# BigBus_XXL_Breed_Error.net
KiCad netlist of a schematic drawn in EAGLE
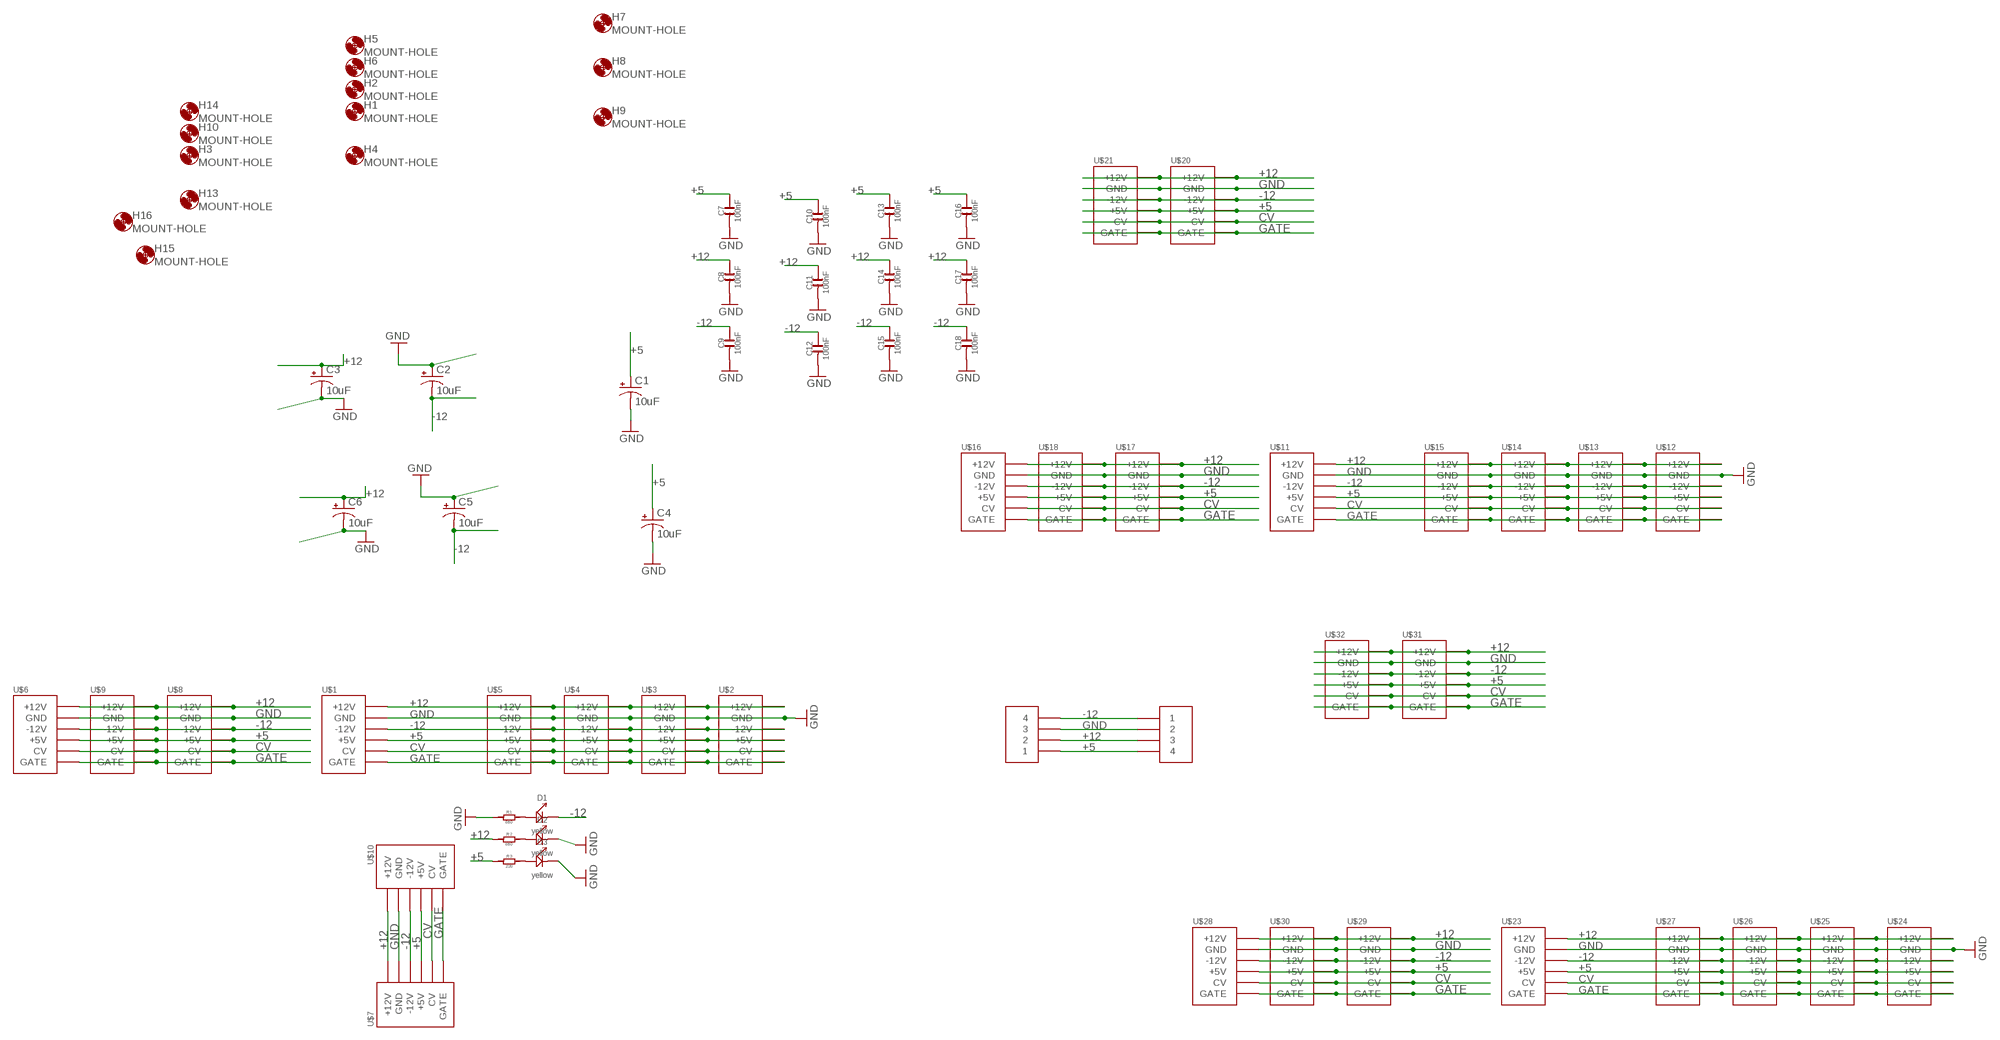
[diagram p0: schematic, sheet 1]

(export (version "E")
  (design (tool "Eeschema 10.0.6"))
  (components
    (comp (ref "C1")
      (value "10uF")
      (footprint "eagle-import:PANASONIC_D")
      (libsource (lib "eagle-import") (part "CAP_POLD"))
    )
    (comp (ref "C2")
      (value "10uF")
      (footprint "eagle-import:PANASONIC_D")
      (libsource (lib "eagle-import") (part "CAP_POLD"))
    )
    (comp (ref "C3")
      (value "10uF")
      (footprint "eagle-import:PANASONIC_D")
      (libsource (lib "eagle-import") (part "CAP_POLD"))
    )
    (comp (ref "C4")
      (value "10uF")
      (footprint "eagle-import:PANASONIC_D")
      (libsource (lib "eagle-import") (part "CAP_POLD"))
    )
    (comp (ref "C5")
      (value "10uF")
      (footprint "eagle-import:PANASONIC_D")
      (libsource (lib "eagle-import") (part "CAP_POLD"))
    )
    (comp (ref "C6")
      (value "10uF")
      (footprint "eagle-import:PANASONIC_D")
      (libsource (lib "eagle-import") (part "CAP_POLD"))
    )
    (comp (ref "C7")
      (value "100nF")
      (footprint "eagle-import:C0603")
      (libsource (lib "eagle-import") (part "C-0603"))
    )
    (comp (ref "C8")
      (value "100nF")
      (footprint "eagle-import:C0603")
      (libsource (lib "eagle-import") (part "C-0603"))
    )
    (comp (ref "C9")
      (value "100nF")
      (footprint "eagle-import:C0603")
      (libsource (lib "eagle-import") (part "C-0603"))
    )
    (comp (ref "C10")
      (value "100nF")
      (footprint "eagle-import:C0603")
      (libsource (lib "eagle-import") (part "C-0603"))
    )
    (comp (ref "C11")
      (value "100nF")
      (footprint "eagle-import:C0603")
      (libsource (lib "eagle-import") (part "C-0603"))
    )
    (comp (ref "C12")
      (value "100nF")
      (footprint "eagle-import:C0603")
      (libsource (lib "eagle-import") (part "C-0603"))
    )
    (comp (ref "C13")
      (value "100nF")
      (footprint "eagle-import:C0603")
      (libsource (lib "eagle-import") (part "C-0603"))
    )
    (comp (ref "C14")
      (value "100nF")
      (footprint "eagle-import:C0603")
      (libsource (lib "eagle-import") (part "C-0603"))
    )
    (comp (ref "C15")
      (value "100nF")
      (footprint "eagle-import:C0603")
      (libsource (lib "eagle-import") (part "C-0603"))
    )
    (comp (ref "C16")
      (value "100nF")
      (footprint "eagle-import:C0603")
      (libsource (lib "eagle-import") (part "C-0603"))
    )
    (comp (ref "C17")
      (value "100nF")
      (footprint "eagle-import:C0603")
      (libsource (lib "eagle-import") (part "C-0603"))
    )
    (comp (ref "C18")
      (value "100nF")
      (footprint "eagle-import:C0603")
      (libsource (lib "eagle-import") (part "C-0603"))
    )
    (comp (ref "D1")
      (value "yellow")
      (footprint "eagle-import:LED0603")
      (libsource (lib "eagle-import") (part "LED"))
    )
    (comp (ref "D2")
      (value "yellow")
      (footprint "eagle-import:LED0603")
      (libsource (lib "eagle-import") (part "LED"))
    )
    (comp (ref "D3")
      (value "yellow")
      (footprint "eagle-import:LED0603")
      (libsource (lib "eagle-import") (part "LED"))
    )
    (comp (ref "H1")
      (value "MOUNT-HOLE")
      (footprint "eagle-import:3.2-NOMARKINGS-SMALLSAFEZONE")
      (libsource (lib "eagle-import") (part "MOUNT-HOLE"))
    )
    (comp (ref "H2")
      (value "MOUNT-HOLE")
      (footprint "eagle-import:3.2-NOMARKINGS-SMALLSAFEZONE")
      (libsource (lib "eagle-import") (part "MOUNT-HOLE"))
    )
    (comp (ref "H3")
      (value "MOUNT-HOLE")
      (footprint "eagle-import:3.2-NOMARKINGS-SMALLSAFEZONE")
      (libsource (lib "eagle-import") (part "MOUNT-HOLE"))
    )
    (comp (ref "H4")
      (value "MOUNT-HOLE")
      (footprint "eagle-import:3.2-NOMARKINGS-SMALLSAFEZONE")
      (libsource (lib "eagle-import") (part "MOUNT-HOLE"))
    )
    (comp (ref "H5")
      (value "MOUNT-HOLE")
      (footprint "eagle-import:3.2-NOMARKINGS-SMALLSAFEZONE")
      (libsource (lib "eagle-import") (part "MOUNT-HOLE"))
    )
    (comp (ref "H6")
      (value "MOUNT-HOLE")
      (footprint "eagle-import:3.2-NOMARKINGS-SMALLSAFEZONE")
      (libsource (lib "eagle-import") (part "MOUNT-HOLE"))
    )
    (comp (ref "H7")
      (value "MOUNT-HOLE")
      (footprint "eagle-import:3.2-NOMARKINGS-SMALLSAFEZONE")
      (libsource (lib "eagle-import") (part "MOUNT-HOLE"))
    )
    (comp (ref "H8")
      (value "MOUNT-HOLE")
      (footprint "eagle-import:3.2-NOMARKINGS-SMALLSAFEZONE")
      (libsource (lib "eagle-import") (part "MOUNT-HOLE"))
    )
    (comp (ref "H9")
      (value "MOUNT-HOLE")
      (footprint "eagle-import:3.2-NOMARKINGS-SMALLSAFEZONE")
      (libsource (lib "eagle-import") (part "MOUNT-HOLE"))
    )
    (comp (ref "H10")
      (value "MOUNT-HOLE")
      (footprint "eagle-import:3.2-NOMARKINGS-SMALLSAFEZONE")
      (libsource (lib "eagle-import") (part "MOUNT-HOLE"))
    )
    (comp (ref "H13")
      (value "MOUNT-HOLE")
      (footprint "eagle-import:3.2-NOMARKINGS-SMALLSAFEZONE")
      (libsource (lib "eagle-import") (part "MOUNT-HOLE"))
    )
    (comp (ref "H14")
      (value "MOUNT-HOLE")
      (footprint "eagle-import:3.2-NOMARKINGS-SMALLSAFEZONE")
      (libsource (lib "eagle-import") (part "MOUNT-HOLE"))
    )
    (comp (ref "H15")
      (value "MOUNT-HOLE")
      (footprint "eagle-import:3.2-NOMARKINGS-SMALLSAFEZONE")
      (libsource (lib "eagle-import") (part "MOUNT-HOLE"))
    )
    (comp (ref "H16")
      (value "MOUNT-HOLE")
      (footprint "eagle-import:3.2-NOMARKINGS-SMALLSAFEZONE")
      (libsource (lib "eagle-import") (part "MOUNT-HOLE"))
    )
    (comp (ref "R1")
      (value "680")
      (footprint "eagle-import:R0603")
      (libsource (lib "eagle-import") (part "R-0603"))
    )
    (comp (ref "R2")
      (value "680")
      (footprint "eagle-import:R0603")
      (libsource (lib "eagle-import") (part "R-0603"))
    )
    (comp (ref "R3")
      (value "220")
      (footprint "eagle-import:R0603")
      (libsource (lib "eagle-import") (part "R-0603"))
    )
    (comp (ref "U$1")
      (value "POWER_SHROUDED_NOTEXT")
      (footprint "eagle-import:POWER_16_SHROUDED_NOTEXT")
      (libsource (lib "eagle-import") (part "POWER_SHROUDED_NOTEXT"))
    )
    (comp (ref "U$2")
      (value "POWER_SHROUDED_NOTEXT")
      (footprint "eagle-import:POWER_16_SHROUDED_NOTEXT")
      (libsource (lib "eagle-import") (part "POWER_SHROUDED_NOTEXT"))
    )
    (comp (ref "U$3")
      (value "POWER_SHROUDED_NOTEXT")
      (footprint "eagle-import:POWER_16_SHROUDED_NOTEXT")
      (libsource (lib "eagle-import") (part "POWER_SHROUDED_NOTEXT"))
    )
    (comp (ref "U$4")
      (value "POWER_SHROUDED_NOTEXT")
      (footprint "eagle-import:POWER_16_SHROUDED_NOTEXT")
      (libsource (lib "eagle-import") (part "POWER_SHROUDED_NOTEXT"))
    )
    (comp (ref "U$5")
      (value "POWER_SHROUDED_NOTEXT")
      (footprint "eagle-import:POWER_16_SHROUDED_NOTEXT")
      (libsource (lib "eagle-import") (part "POWER_SHROUDED_NOTEXT"))
    )
    (comp (ref "U$6")
      (value "POWER_SHROUDED_NOTEXT")
      (footprint "eagle-import:POWER_16_SHROUDED_NOTEXT")
      (libsource (lib "eagle-import") (part "POWER_SHROUDED_NOTEXT"))
    )
    (comp (ref "U$7")
      (value "POWER_SHROUDED_NOTEXT")
      (footprint "eagle-import:POWER_16_SHROUDED_NOTEXT")
      (libsource (lib "eagle-import") (part "POWER_SHROUDED_NOTEXT"))
    )
    (comp (ref "U$8")
      (value "POWER_SHROUDED_NOTEXT")
      (footprint "eagle-import:POWER_16_SHROUDED_NOTEXT")
      (libsource (lib "eagle-import") (part "POWER_SHROUDED_NOTEXT"))
    )
    (comp (ref "U$9")
      (value "POWER_SHROUDED_NOTEXT")
      (footprint "eagle-import:POWER_16_SHROUDED_NOTEXT")
      (libsource (lib "eagle-import") (part "POWER_SHROUDED_NOTEXT"))
    )
    (comp (ref "U$10")
      (value "POWER_SHROUDED_NOTEXT")
      (footprint "eagle-import:POWER_16_SHROUDED_NOTEXT")
      (libsource (lib "eagle-import") (part "POWER_SHROUDED_NOTEXT"))
    )
    (comp (ref "U$11")
      (value "POWER_SHROUDED_NOTEXT")
      (footprint "eagle-import:POWER_16_SHROUDED_NOTEXT")
      (libsource (lib "eagle-import") (part "POWER_SHROUDED_NOTEXT"))
    )
    (comp (ref "U$12")
      (value "POWER_SHROUDED_NOTEXT")
      (footprint "eagle-import:POWER_16_SHROUDED_NOTEXT")
      (libsource (lib "eagle-import") (part "POWER_SHROUDED_NOTEXT"))
    )
    (comp (ref "U$13")
      (value "POWER_SHROUDED_NOTEXT")
      (footprint "eagle-import:POWER_16_SHROUDED_NOTEXT")
      (libsource (lib "eagle-import") (part "POWER_SHROUDED_NOTEXT"))
    )
    (comp (ref "U$14")
      (value "POWER_SHROUDED_NOTEXT")
      (footprint "eagle-import:POWER_16_SHROUDED_NOTEXT")
      (libsource (lib "eagle-import") (part "POWER_SHROUDED_NOTEXT"))
    )
    (comp (ref "U$15")
      (value "POWER_SHROUDED_NOTEXT")
      (footprint "eagle-import:POWER_16_SHROUDED_NOTEXT")
      (libsource (lib "eagle-import") (part "POWER_SHROUDED_NOTEXT"))
    )
    (comp (ref "U$16")
      (value "POWER_SHROUDED_NOTEXT")
      (footprint "eagle-import:POWER_16_SHROUDED_NOTEXT")
      (libsource (lib "eagle-import") (part "POWER_SHROUDED_NOTEXT"))
    )
    (comp (ref "U$17")
      (value "POWER_SHROUDED_NOTEXT")
      (footprint "eagle-import:POWER_16_SHROUDED_NOTEXT")
      (libsource (lib "eagle-import") (part "POWER_SHROUDED_NOTEXT"))
    )
    (comp (ref "U$18")
      (value "POWER_SHROUDED_NOTEXT")
      (footprint "eagle-import:POWER_16_SHROUDED_NOTEXT")
      (libsource (lib "eagle-import") (part "POWER_SHROUDED_NOTEXT"))
    )
    (comp (ref "U$19")
      (value "4PIN5MM")
      (footprint "eagle-import:4PIN5MM")
      (libsource (lib "eagle-import") (part "4PIN5MM"))
    )
    (comp (ref "U$20")
      (value "POWER_SHROUDED_NOTEXT")
      (footprint "eagle-import:POWER_16_SHROUDED_NOTEXT")
      (libsource (lib "eagle-import") (part "POWER_SHROUDED_NOTEXT"))
    )
    (comp (ref "U$21")
      (value "POWER_SHROUDED_NOTEXT")
      (footprint "eagle-import:POWER_16_SHROUDED_NOTEXT")
      (libsource (lib "eagle-import") (part "POWER_SHROUDED_NOTEXT"))
    )
    (comp (ref "U$22")
      (value "4PIN5MM")
      (footprint "eagle-import:4PIN5MM")
      (libsource (lib "eagle-import") (part "4PIN5MM"))
    )
    (comp (ref "U$23")
      (value "POWER_SHROUDED_NOTEXT")
      (footprint "eagle-import:POWER_16_SHROUDED_NOTEXT")
      (libsource (lib "eagle-import") (part "POWER_SHROUDED_NOTEXT"))
    )
    (comp (ref "U$24")
      (value "POWER_SHROUDED_NOTEXT")
      (footprint "eagle-import:POWER_16_SHROUDED_NOTEXT")
      (libsource (lib "eagle-import") (part "POWER_SHROUDED_NOTEXT"))
    )
    (comp (ref "U$25")
      (value "POWER_SHROUDED_NOTEXT")
      (footprint "eagle-import:POWER_16_SHROUDED_NOTEXT")
      (libsource (lib "eagle-import") (part "POWER_SHROUDED_NOTEXT"))
    )
    (comp (ref "U$26")
      (value "POWER_SHROUDED_NOTEXT")
      (footprint "eagle-import:POWER_16_SHROUDED_NOTEXT")
      (libsource (lib "eagle-import") (part "POWER_SHROUDED_NOTEXT"))
    )
    (comp (ref "U$27")
      (value "POWER_SHROUDED_NOTEXT")
      (footprint "eagle-import:POWER_16_SHROUDED_NOTEXT")
      (libsource (lib "eagle-import") (part "POWER_SHROUDED_NOTEXT"))
    )
    (comp (ref "U$28")
      (value "POWER_SHROUDED_NOTEXT")
      (footprint "eagle-import:POWER_16_SHROUDED_NOTEXT")
      (libsource (lib "eagle-import") (part "POWER_SHROUDED_NOTEXT"))
    )
    (comp (ref "U$29")
      (value "POWER_SHROUDED_NOTEXT")
      (footprint "eagle-import:POWER_16_SHROUDED_NOTEXT")
      (libsource (lib "eagle-import") (part "POWER_SHROUDED_NOTEXT"))
    )
    (comp (ref "U$30")
      (value "POWER_SHROUDED_NOTEXT")
      (footprint "eagle-import:POWER_16_SHROUDED_NOTEXT")
      (libsource (lib "eagle-import") (part "POWER_SHROUDED_NOTEXT"))
    )
    (comp (ref "U$31")
      (value "POWER_SHROUDED_NOTEXT")
      (footprint "eagle-import:POWER_16_SHROUDED_NOTEXT")
      (libsource (lib "eagle-import") (part "POWER_SHROUDED_NOTEXT"))
    )
    (comp (ref "U$32")
      (value "POWER_SHROUDED_NOTEXT")
      (footprint "eagle-import:POWER_16_SHROUDED_NOTEXT")
      (libsource (lib "eagle-import") (part "POWER_SHROUDED_NOTEXT"))
    )
  )
  (nets
    (net (code "1") (name "/+5") (class "Default")
      (node (ref "C1") (pin "+") (pinfunction "+_+") (pintype "passive"))
      (node (ref "C10") (pin "2") (pinfunction "2_2") (pintype "bidirectional"))
      (node (ref "C13") (pin "2") (pinfunction "2_2") (pintype "bidirectional"))
      (node (ref "C16") (pin "2") (pinfunction "2_2") (pintype "bidirectional"))
      (node (ref "C4") (pin "+") (pinfunction "+_+") (pintype "passive"))
      (node (ref "C7") (pin "2") (pinfunction "2_2") (pintype "bidirectional"))
      (node (ref "R3") (pin "1") (pinfunction "1_1") (pintype "bidirectional"))
      (node (ref "U$1") (pin "11") (pinfunction "+5V_11") (pintype "bidirectional"))
      (node (ref "U$1") (pin "12") (pinfunction "+5V_12") (pintype "bidirectional"))
      (node (ref "U$10") (pin "11") (pinfunction "+5V_11") (pintype "bidirectional"))
      (node (ref "U$10") (pin "12") (pinfunction "+5V_12") (pintype "bidirectional"))
      (node (ref "U$11") (pin "11") (pinfunction "+5V_11") (pintype "bidirectional"))
      (node (ref "U$11") (pin "12") (pinfunction "+5V_12") (pintype "bidirectional"))
      (node (ref "U$12") (pin "11") (pinfunction "+5V_11") (pintype "bidirectional"))
      (node (ref "U$12") (pin "12") (pinfunction "+5V_12") (pintype "bidirectional"))
      (node (ref "U$13") (pin "11") (pinfunction "+5V_11") (pintype "bidirectional"))
      (node (ref "U$13") (pin "12") (pinfunction "+5V_12") (pintype "bidirectional"))
      (node (ref "U$14") (pin "11") (pinfunction "+5V_11") (pintype "bidirectional"))
      (node (ref "U$14") (pin "12") (pinfunction "+5V_12") (pintype "bidirectional"))
      (node (ref "U$15") (pin "11") (pinfunction "+5V_11") (pintype "bidirectional"))
      (node (ref "U$15") (pin "12") (pinfunction "+5V_12") (pintype "bidirectional"))
      (node (ref "U$16") (pin "11") (pinfunction "+5V_11") (pintype "bidirectional"))
      (node (ref "U$16") (pin "12") (pinfunction "+5V_12") (pintype "bidirectional"))
      (node (ref "U$17") (pin "11") (pinfunction "+5V_11") (pintype "bidirectional"))
      (node (ref "U$17") (pin "12") (pinfunction "+5V_12") (pintype "bidirectional"))
      (node (ref "U$18") (pin "11") (pinfunction "+5V_11") (pintype "bidirectional"))
      (node (ref "U$18") (pin "12") (pinfunction "+5V_12") (pintype "bidirectional"))
      (node (ref "U$19") (pin "4") (pinfunction "4_4") (pintype "bidirectional"))
      (node (ref "U$2") (pin "11") (pinfunction "+5V_11") (pintype "bidirectional"))
      (node (ref "U$2") (pin "12") (pinfunction "+5V_12") (pintype "bidirectional"))
      (node (ref "U$20") (pin "11") (pinfunction "+5V_11") (pintype "bidirectional"))
      (node (ref "U$20") (pin "12") (pinfunction "+5V_12") (pintype "bidirectional"))
      (node (ref "U$21") (pin "11") (pinfunction "+5V_11") (pintype "bidirectional"))
      (node (ref "U$21") (pin "12") (pinfunction "+5V_12") (pintype "bidirectional"))
      (node (ref "U$22") (pin "1") (pinfunction "1_1") (pintype "bidirectional"))
      (node (ref "U$23") (pin "11") (pinfunction "+5V_11") (pintype "bidirectional"))
      (node (ref "U$23") (pin "12") (pinfunction "+5V_12") (pintype "bidirectional"))
      (node (ref "U$24") (pin "11") (pinfunction "+5V_11") (pintype "bidirectional"))
      (node (ref "U$24") (pin "12") (pinfunction "+5V_12") (pintype "bidirectional"))
      (node (ref "U$25") (pin "11") (pinfunction "+5V_11") (pintype "bidirectional"))
      (node (ref "U$25") (pin "12") (pinfunction "+5V_12") (pintype "bidirectional"))
      (node (ref "U$26") (pin "11") (pinfunction "+5V_11") (pintype "bidirectional"))
      (node (ref "U$26") (pin "12") (pinfunction "+5V_12") (pintype "bidirectional"))
      (node (ref "U$27") (pin "11") (pinfunction "+5V_11") (pintype "bidirectional"))
      (node (ref "U$27") (pin "12") (pinfunction "+5V_12") (pintype "bidirectional"))
      (node (ref "U$28") (pin "11") (pinfunction "+5V_11") (pintype "bidirectional"))
      (node (ref "U$28") (pin "12") (pinfunction "+5V_12") (pintype "bidirectional"))
      (node (ref "U$29") (pin "11") (pinfunction "+5V_11") (pintype "bidirectional"))
      (node (ref "U$29") (pin "12") (pinfunction "+5V_12") (pintype "bidirectional"))
      (node (ref "U$3") (pin "11") (pinfunction "+5V_11") (pintype "bidirectional"))
      (node (ref "U$3") (pin "12") (pinfunction "+5V_12") (pintype "bidirectional"))
      (node (ref "U$30") (pin "11") (pinfunction "+5V_11") (pintype "bidirectional"))
      (node (ref "U$30") (pin "12") (pinfunction "+5V_12") (pintype "bidirectional"))
      (node (ref "U$31") (pin "11") (pinfunction "+5V_11") (pintype "bidirectional"))
      (node (ref "U$31") (pin "12") (pinfunction "+5V_12") (pintype "bidirectional"))
      (node (ref "U$32") (pin "11") (pinfunction "+5V_11") (pintype "bidirectional"))
      (node (ref "U$32") (pin "12") (pinfunction "+5V_12") (pintype "bidirectional"))
      (node (ref "U$4") (pin "11") (pinfunction "+5V_11") (pintype "bidirectional"))
      (node (ref "U$4") (pin "12") (pinfunction "+5V_12") (pintype "bidirectional"))
      (node (ref "U$5") (pin "11") (pinfunction "+5V_11") (pintype "bidirectional"))
      (node (ref "U$5") (pin "12") (pinfunction "+5V_12") (pintype "bidirectional"))
      (node (ref "U$6") (pin "11") (pinfunction "+5V_11") (pintype "bidirectional"))
      (node (ref "U$6") (pin "12") (pinfunction "+5V_12") (pintype "bidirectional"))
      (node (ref "U$7") (pin "11") (pinfunction "+5V_11") (pintype "bidirectional"))
      (node (ref "U$7") (pin "12") (pinfunction "+5V_12") (pintype "bidirectional"))
      (node (ref "U$8") (pin "11") (pinfunction "+5V_11") (pintype "bidirectional"))
      (node (ref "U$8") (pin "12") (pinfunction "+5V_12") (pintype "bidirectional"))
      (node (ref "U$9") (pin "11") (pinfunction "+5V_11") (pintype "bidirectional"))
      (node (ref "U$9") (pin "12") (pinfunction "+5V_12") (pintype "bidirectional"))
    )
    (net (code "2") (name "/+12") (class "Default")
      (node (ref "C11") (pin "2") (pinfunction "2_2") (pintype "bidirectional"))
      (node (ref "C14") (pin "2") (pinfunction "2_2") (pintype "bidirectional"))
      (node (ref "C17") (pin "2") (pinfunction "2_2") (pintype "bidirectional"))
      (node (ref "C3") (pin "+") (pinfunction "+_+") (pintype "passive"))
      (node (ref "C6") (pin "+") (pinfunction "+_+") (pintype "passive"))
      (node (ref "C8") (pin "2") (pinfunction "2_2") (pintype "bidirectional"))
      (node (ref "R2") (pin "1") (pinfunction "1_1") (pintype "bidirectional"))
      (node (ref "U$1") (pin "10") (pinfunction "+12V_10") (pintype "bidirectional"))
      (node (ref "U$1") (pin "9") (pinfunction "+12V_9") (pintype "bidirectional"))
      (node (ref "U$10") (pin "10") (pinfunction "+12V_10") (pintype "bidirectional"))
      (node (ref "U$10") (pin "9") (pinfunction "+12V_9") (pintype "bidirectional"))
      (node (ref "U$11") (pin "10") (pinfunction "+12V_10") (pintype "bidirectional"))
      (node (ref "U$11") (pin "9") (pinfunction "+12V_9") (pintype "bidirectional"))
      (node (ref "U$12") (pin "10") (pinfunction "+12V_10") (pintype "bidirectional"))
      (node (ref "U$12") (pin "9") (pinfunction "+12V_9") (pintype "bidirectional"))
      (node (ref "U$13") (pin "10") (pinfunction "+12V_10") (pintype "bidirectional"))
      (node (ref "U$13") (pin "9") (pinfunction "+12V_9") (pintype "bidirectional"))
      (node (ref "U$14") (pin "10") (pinfunction "+12V_10") (pintype "bidirectional"))
      (node (ref "U$14") (pin "9") (pinfunction "+12V_9") (pintype "bidirectional"))
      (node (ref "U$15") (pin "10") (pinfunction "+12V_10") (pintype "bidirectional"))
      (node (ref "U$15") (pin "9") (pinfunction "+12V_9") (pintype "bidirectional"))
      (node (ref "U$16") (pin "10") (pinfunction "+12V_10") (pintype "bidirectional"))
      (node (ref "U$16") (pin "9") (pinfunction "+12V_9") (pintype "bidirectional"))
      (node (ref "U$17") (pin "10") (pinfunction "+12V_10") (pintype "bidirectional"))
      (node (ref "U$17") (pin "9") (pinfunction "+12V_9") (pintype "bidirectional"))
      (node (ref "U$18") (pin "10") (pinfunction "+12V_10") (pintype "bidirectional"))
      (node (ref "U$18") (pin "9") (pinfunction "+12V_9") (pintype "bidirectional"))
      (node (ref "U$19") (pin "3") (pinfunction "3_3") (pintype "bidirectional"))
      (node (ref "U$2") (pin "10") (pinfunction "+12V_10") (pintype "bidirectional"))
      (node (ref "U$2") (pin "9") (pinfunction "+12V_9") (pintype "bidirectional"))
      (node (ref "U$20") (pin "10") (pinfunction "+12V_10") (pintype "bidirectional"))
      (node (ref "U$20") (pin "9") (pinfunction "+12V_9") (pintype "bidirectional"))
      (node (ref "U$21") (pin "10") (pinfunction "+12V_10") (pintype "bidirectional"))
      (node (ref "U$21") (pin "9") (pinfunction "+12V_9") (pintype "bidirectional"))
      (node (ref "U$22") (pin "2") (pinfunction "2_2") (pintype "bidirectional"))
      (node (ref "U$23") (pin "10") (pinfunction "+12V_10") (pintype "bidirectional"))
      (node (ref "U$23") (pin "9") (pinfunction "+12V_9") (pintype "bidirectional"))
      (node (ref "U$24") (pin "10") (pinfunction "+12V_10") (pintype "bidirectional"))
      (node (ref "U$24") (pin "9") (pinfunction "+12V_9") (pintype "bidirectional"))
      (node (ref "U$25") (pin "10") (pinfunction "+12V_10") (pintype "bidirectional"))
      (node (ref "U$25") (pin "9") (pinfunction "+12V_9") (pintype "bidirectional"))
      (node (ref "U$26") (pin "10") (pinfunction "+12V_10") (pintype "bidirectional"))
      (node (ref "U$26") (pin "9") (pinfunction "+12V_9") (pintype "bidirectional"))
      (node (ref "U$27") (pin "10") (pinfunction "+12V_10") (pintype "bidirectional"))
      (node (ref "U$27") (pin "9") (pinfunction "+12V_9") (pintype "bidirectional"))
      (node (ref "U$28") (pin "10") (pinfunction "+12V_10") (pintype "bidirectional"))
      (node (ref "U$28") (pin "9") (pinfunction "+12V_9") (pintype "bidirectional"))
      (node (ref "U$29") (pin "10") (pinfunction "+12V_10") (pintype "bidirectional"))
      (node (ref "U$29") (pin "9") (pinfunction "+12V_9") (pintype "bidirectional"))
      (node (ref "U$3") (pin "10") (pinfunction "+12V_10") (pintype "bidirectional"))
      (node (ref "U$3") (pin "9") (pinfunction "+12V_9") (pintype "bidirectional"))
      (node (ref "U$30") (pin "10") (pinfunction "+12V_10") (pintype "bidirectional"))
      (node (ref "U$30") (pin "9") (pinfunction "+12V_9") (pintype "bidirectional"))
      (node (ref "U$31") (pin "10") (pinfunction "+12V_10") (pintype "bidirectional"))
      (node (ref "U$31") (pin "9") (pinfunction "+12V_9") (pintype "bidirectional"))
      (node (ref "U$32") (pin "10") (pinfunction "+12V_10") (pintype "bidirectional"))
      (node (ref "U$32") (pin "9") (pinfunction "+12V_9") (pintype "bidirectional"))
      (node (ref "U$4") (pin "10") (pinfunction "+12V_10") (pintype "bidirectional"))
      (node (ref "U$4") (pin "9") (pinfunction "+12V_9") (pintype "bidirectional"))
      (node (ref "U$5") (pin "10") (pinfunction "+12V_10") (pintype "bidirectional"))
      (node (ref "U$5") (pin "9") (pinfunction "+12V_9") (pintype "bidirectional"))
      (node (ref "U$6") (pin "10") (pinfunction "+12V_10") (pintype "bidirectional"))
      (node (ref "U$6") (pin "9") (pinfunction "+12V_9") (pintype "bidirectional"))
      (node (ref "U$7") (pin "10") (pinfunction "+12V_10") (pintype "bidirectional"))
      (node (ref "U$7") (pin "9") (pinfunction "+12V_9") (pintype "bidirectional"))
      (node (ref "U$8") (pin "10") (pinfunction "+12V_10") (pintype "bidirectional"))
      (node (ref "U$8") (pin "9") (pinfunction "+12V_9") (pintype "bidirectional"))
      (node (ref "U$9") (pin "10") (pinfunction "+12V_10") (pintype "bidirectional"))
      (node (ref "U$9") (pin "9") (pinfunction "+12V_9") (pintype "bidirectional"))
    )
    (net (code "3") (name "/-12") (class "Default")
      (node (ref "C12") (pin "2") (pinfunction "2_2") (pintype "bidirectional"))
      (node (ref "C15") (pin "2") (pinfunction "2_2") (pintype "bidirectional"))
      (node (ref "C18") (pin "2") (pinfunction "2_2") (pintype "bidirectional"))
      (node (ref "C2") (pin "-") (pinfunction "-_-") (pintype "passive"))
      (node (ref "C5") (pin "-") (pinfunction "-_-") (pintype "passive"))
      (node (ref "C9") (pin "2") (pinfunction "2_2") (pintype "bidirectional"))
      (node (ref "D1") (pin "-") (pinfunction "-_-") (pintype "passive"))
      (node (ref "U$1") (pin "1") (pinfunction "-12V_1") (pintype "bidirectional"))
      (node (ref "U$1") (pin "2") (pinfunction "-12V_2") (pintype "bidirectional"))
      (node (ref "U$10") (pin "1") (pinfunction "-12V_1") (pintype "bidirectional"))
      (node (ref "U$10") (pin "2") (pinfunction "-12V_2") (pintype "bidirectional"))
      (node (ref "U$11") (pin "1") (pinfunction "-12V_1") (pintype "bidirectional"))
      (node (ref "U$11") (pin "2") (pinfunction "-12V_2") (pintype "bidirectional"))
      (node (ref "U$12") (pin "1") (pinfunction "-12V_1") (pintype "bidirectional"))
      (node (ref "U$12") (pin "2") (pinfunction "-12V_2") (pintype "bidirectional"))
      (node (ref "U$13") (pin "1") (pinfunction "-12V_1") (pintype "bidirectional"))
      (node (ref "U$13") (pin "2") (pinfunction "-12V_2") (pintype "bidirectional"))
      (node (ref "U$14") (pin "1") (pinfunction "-12V_1") (pintype "bidirectional"))
      (node (ref "U$14") (pin "2") (pinfunction "-12V_2") (pintype "bidirectional"))
      (node (ref "U$15") (pin "1") (pinfunction "-12V_1") (pintype "bidirectional"))
      (node (ref "U$15") (pin "2") (pinfunction "-12V_2") (pintype "bidirectional"))
      (node (ref "U$16") (pin "1") (pinfunction "-12V_1") (pintype "bidirectional"))
      (node (ref "U$16") (pin "2") (pinfunction "-12V_2") (pintype "bidirectional"))
      (node (ref "U$17") (pin "1") (pinfunction "-12V_1") (pintype "bidirectional"))
      (node (ref "U$17") (pin "2") (pinfunction "-12V_2") (pintype "bidirectional"))
      (node (ref "U$18") (pin "1") (pinfunction "-12V_1") (pintype "bidirectional"))
      (node (ref "U$18") (pin "2") (pinfunction "-12V_2") (pintype "bidirectional"))
      (node (ref "U$19") (pin "1") (pinfunction "1_1") (pintype "bidirectional"))
      (node (ref "U$2") (pin "1") (pinfunction "-12V_1") (pintype "bidirectional"))
      (node (ref "U$2") (pin "2") (pinfunction "-12V_2") (pintype "bidirectional"))
      (node (ref "U$20") (pin "1") (pinfunction "-12V_1") (pintype "bidirectional"))
      (node (ref "U$20") (pin "2") (pinfunction "-12V_2") (pintype "bidirectional"))
      (node (ref "U$21") (pin "1") (pinfunction "-12V_1") (pintype "bidirectional"))
      (node (ref "U$21") (pin "2") (pinfunction "-12V_2") (pintype "bidirectional"))
      (node (ref "U$22") (pin "4") (pinfunction "4_4") (pintype "bidirectional"))
      (node (ref "U$23") (pin "1") (pinfunction "-12V_1") (pintype "bidirectional"))
      (node (ref "U$23") (pin "2") (pinfunction "-12V_2") (pintype "bidirectional"))
      (node (ref "U$24") (pin "1") (pinfunction "-12V_1") (pintype "bidirectional"))
      (node (ref "U$24") (pin "2") (pinfunction "-12V_2") (pintype "bidirectional"))
      (node (ref "U$25") (pin "1") (pinfunction "-12V_1") (pintype "bidirectional"))
      (node (ref "U$25") (pin "2") (pinfunction "-12V_2") (pintype "bidirectional"))
      (node (ref "U$26") (pin "1") (pinfunction "-12V_1") (pintype "bidirectional"))
      (node (ref "U$26") (pin "2") (pinfunction "-12V_2") (pintype "bidirectional"))
      (node (ref "U$27") (pin "1") (pinfunction "-12V_1") (pintype "bidirectional"))
      (node (ref "U$27") (pin "2") (pinfunction "-12V_2") (pintype "bidirectional"))
      (node (ref "U$28") (pin "1") (pinfunction "-12V_1") (pintype "bidirectional"))
      (node (ref "U$28") (pin "2") (pinfunction "-12V_2") (pintype "bidirectional"))
      (node (ref "U$29") (pin "1") (pinfunction "-12V_1") (pintype "bidirectional"))
      (node (ref "U$29") (pin "2") (pinfunction "-12V_2") (pintype "bidirectional"))
      (node (ref "U$3") (pin "1") (pinfunction "-12V_1") (pintype "bidirectional"))
      (node (ref "U$3") (pin "2") (pinfunction "-12V_2") (pintype "bidirectional"))
      (node (ref "U$30") (pin "1") (pinfunction "-12V_1") (pintype "bidirectional"))
      (node (ref "U$30") (pin "2") (pinfunction "-12V_2") (pintype "bidirectional"))
      (node (ref "U$31") (pin "1") (pinfunction "-12V_1") (pintype "bidirectional"))
      (node (ref "U$31") (pin "2") (pinfunction "-12V_2") (pintype "bidirectional"))
      (node (ref "U$32") (pin "1") (pinfunction "-12V_1") (pintype "bidirectional"))
      (node (ref "U$32") (pin "2") (pinfunction "-12V_2") (pintype "bidirectional"))
      (node (ref "U$4") (pin "1") (pinfunction "-12V_1") (pintype "bidirectional"))
      (node (ref "U$4") (pin "2") (pinfunction "-12V_2") (pintype "bidirectional"))
      (node (ref "U$5") (pin "1") (pinfunction "-12V_1") (pintype "bidirectional"))
      (node (ref "U$5") (pin "2") (pinfunction "-12V_2") (pintype "bidirectional"))
      (node (ref "U$6") (pin "1") (pinfunction "-12V_1") (pintype "bidirectional"))
      (node (ref "U$6") (pin "2") (pinfunction "-12V_2") (pintype "bidirectional"))
      (node (ref "U$7") (pin "1") (pinfunction "-12V_1") (pintype "bidirectional"))
      (node (ref "U$7") (pin "2") (pinfunction "-12V_2") (pintype "bidirectional"))
      (node (ref "U$8") (pin "1") (pinfunction "-12V_1") (pintype "bidirectional"))
      (node (ref "U$8") (pin "2") (pinfunction "-12V_2") (pintype "bidirectional"))
      (node (ref "U$9") (pin "1") (pinfunction "-12V_1") (pintype "bidirectional"))
      (node (ref "U$9") (pin "2") (pinfunction "-12V_2") (pintype "bidirectional"))
    )
    (net (code "4") (name "/CV") (class "Default")
      (node (ref "U$1") (pin "13") (pinfunction "CV_13") (pintype "bidirectional"))
      (node (ref "U$1") (pin "14") (pinfunction "CV_14") (pintype "bidirectional"))
      (node (ref "U$10") (pin "13") (pinfunction "CV_13") (pintype "bidirectional"))
      (node (ref "U$10") (pin "14") (pinfunction "CV_14") (pintype "bidirectional"))
      (node (ref "U$11") (pin "13") (pinfunction "CV_13") (pintype "bidirectional"))
      (node (ref "U$11") (pin "14") (pinfunction "CV_14") (pintype "bidirectional"))
      (node (ref "U$12") (pin "13") (pinfunction "CV_13") (pintype "bidirectional"))
      (node (ref "U$12") (pin "14") (pinfunction "CV_14") (pintype "bidirectional"))
      (node (ref "U$13") (pin "13") (pinfunction "CV_13") (pintype "bidirectional"))
      (node (ref "U$13") (pin "14") (pinfunction "CV_14") (pintype "bidirectional"))
      (node (ref "U$14") (pin "13") (pinfunction "CV_13") (pintype "bidirectional"))
      (node (ref "U$14") (pin "14") (pinfunction "CV_14") (pintype "bidirectional"))
      (node (ref "U$15") (pin "13") (pinfunction "CV_13") (pintype "bidirectional"))
      (node (ref "U$15") (pin "14") (pinfunction "CV_14") (pintype "bidirectional"))
      (node (ref "U$16") (pin "13") (pinfunction "CV_13") (pintype "bidirectional"))
      (node (ref "U$16") (pin "14") (pinfunction "CV_14") (pintype "bidirectional"))
      (node (ref "U$17") (pin "13") (pinfunction "CV_13") (pintype "bidirectional"))
      (node (ref "U$17") (pin "14") (pinfunction "CV_14") (pintype "bidirectional"))
      (node (ref "U$18") (pin "13") (pinfunction "CV_13") (pintype "bidirectional"))
      (node (ref "U$18") (pin "14") (pinfunction "CV_14") (pintype "bidirectional"))
      (node (ref "U$2") (pin "13") (pinfunction "CV_13") (pintype "bidirectional"))
      (node (ref "U$2") (pin "14") (pinfunction "CV_14") (pintype "bidirectional"))
      (node (ref "U$20") (pin "13") (pinfunction "CV_13") (pintype "bidirectional"))
      (node (ref "U$20") (pin "14") (pinfunction "CV_14") (pintype "bidirectional"))
      (node (ref "U$21") (pin "13") (pinfunction "CV_13") (pintype "bidirectional"))
      (node (ref "U$21") (pin "14") (pinfunction "CV_14") (pintype "bidirectional"))
      (node (ref "U$23") (pin "13") (pinfunction "CV_13") (pintype "bidirectional"))
      (node (ref "U$23") (pin "14") (pinfunction "CV_14") (pintype "bidirectional"))
      (node (ref "U$24") (pin "13") (pinfunction "CV_13") (pintype "bidirectional"))
      (node (ref "U$24") (pin "14") (pinfunction "CV_14") (pintype "bidirectional"))
      (node (ref "U$25") (pin "13") (pinfunction "CV_13") (pintype "bidirectional"))
      (node (ref "U$25") (pin "14") (pinfunction "CV_14") (pintype "bidirectional"))
      (node (ref "U$26") (pin "13") (pinfunction "CV_13") (pintype "bidirectional"))
      (node (ref "U$26") (pin "14") (pinfunction "CV_14") (pintype "bidirectional"))
      (node (ref "U$27") (pin "13") (pinfunction "CV_13") (pintype "bidirectional"))
      (node (ref "U$27") (pin "14") (pinfunction "CV_14") (pintype "bidirectional"))
      (node (ref "U$28") (pin "13") (pinfunction "CV_13") (pintype "bidirectional"))
      (node (ref "U$28") (pin "14") (pinfunction "CV_14") (pintype "bidirectional"))
      (node (ref "U$29") (pin "13") (pinfunction "CV_13") (pintype "bidirectional"))
      (node (ref "U$29") (pin "14") (pinfunction "CV_14") (pintype "bidirectional"))
      (node (ref "U$3") (pin "13") (pinfunction "CV_13") (pintype "bidirectional"))
      (node (ref "U$3") (pin "14") (pinfunction "CV_14") (pintype "bidirectional"))
      (node (ref "U$30") (pin "13") (pinfunction "CV_13") (pintype "bidirectional"))
      (node (ref "U$30") (pin "14") (pinfunction "CV_14") (pintype "bidirectional"))
      (node (ref "U$31") (pin "13") (pinfunction "CV_13") (pintype "bidirectional"))
      (node (ref "U$31") (pin "14") (pinfunction "CV_14") (pintype "bidirectional"))
      (node (ref "U$32") (pin "13") (pinfunction "CV_13") (pintype "bidirectional"))
      (node (ref "U$32") (pin "14") (pinfunction "CV_14") (pintype "bidirectional"))
      (node (ref "U$4") (pin "13") (pinfunction "CV_13") (pintype "bidirectional"))
      (node (ref "U$4") (pin "14") (pinfunction "CV_14") (pintype "bidirectional"))
      (node (ref "U$5") (pin "13") (pinfunction "CV_13") (pintype "bidirectional"))
      (node (ref "U$5") (pin "14") (pinfunction "CV_14") (pintype "bidirectional"))
      (node (ref "U$6") (pin "13") (pinfunction "CV_13") (pintype "bidirectional"))
      (node (ref "U$6") (pin "14") (pinfunction "CV_14") (pintype "bidirectional"))
      (node (ref "U$7") (pin "13") (pinfunction "CV_13") (pintype "bidirectional"))
      (node (ref "U$7") (pin "14") (pinfunction "CV_14") (pintype "bidirectional"))
      (node (ref "U$8") (pin "13") (pinfunction "CV_13") (pintype "bidirectional"))
      (node (ref "U$8") (pin "14") (pinfunction "CV_14") (pintype "bidirectional"))
      (node (ref "U$9") (pin "13") (pinfunction "CV_13") (pintype "bidirectional"))
      (node (ref "U$9") (pin "14") (pinfunction "CV_14") (pintype "bidirectional"))
    )
    (net (code "5") (name "/GATE") (class "Default")
      (node (ref "U$1") (pin "15") (pinfunction "GATE_15") (pintype "bidirectional"))
      (node (ref "U$1") (pin "16") (pinfunction "GATE_16") (pintype "bidirectional"))
      (node (ref "U$10") (pin "15") (pinfunction "GATE_15") (pintype "bidirectional"))
      (node (ref "U$10") (pin "16") (pinfunction "GATE_16") (pintype "bidirectional"))
      (node (ref "U$11") (pin "15") (pinfunction "GATE_15") (pintype "bidirectional"))
      (node (ref "U$11") (pin "16") (pinfunction "GATE_16") (pintype "bidirectional"))
      (node (ref "U$12") (pin "15") (pinfunction "GATE_15") (pintype "bidirectional"))
      (node (ref "U$12") (pin "16") (pinfunction "GATE_16") (pintype "bidirectional"))
      (node (ref "U$13") (pin "15") (pinfunction "GATE_15") (pintype "bidirectional"))
      (node (ref "U$13") (pin "16") (pinfunction "GATE_16") (pintype "bidirectional"))
      (node (ref "U$14") (pin "15") (pinfunction "GATE_15") (pintype "bidirectional"))
      (node (ref "U$14") (pin "16") (pinfunction "GATE_16") (pintype "bidirectional"))
      (node (ref "U$15") (pin "15") (pinfunction "GATE_15") (pintype "bidirectional"))
      (node (ref "U$15") (pin "16") (pinfunction "GATE_16") (pintype "bidirectional"))
      (node (ref "U$16") (pin "15") (pinfunction "GATE_15") (pintype "bidirectional"))
      (node (ref "U$16") (pin "16") (pinfunction "GATE_16") (pintype "bidirectional"))
      (node (ref "U$17") (pin "15") (pinfunction "GATE_15") (pintype "bidirectional"))
      (node (ref "U$17") (pin "16") (pinfunction "GATE_16") (pintype "bidirectional"))
      (node (ref "U$18") (pin "15") (pinfunction "GATE_15") (pintype "bidirectional"))
      (node (ref "U$18") (pin "16") (pinfunction "GATE_16") (pintype "bidirectional"))
      (node (ref "U$2") (pin "15") (pinfunction "GATE_15") (pintype "bidirectional"))
      (node (ref "U$2") (pin "16") (pinfunction "GATE_16") (pintype "bidirectional"))
      (node (ref "U$20") (pin "15") (pinfunction "GATE_15") (pintype "bidirectional"))
      (node (ref "U$20") (pin "16") (pinfunction "GATE_16") (pintype "bidirectional"))
      (node (ref "U$21") (pin "15") (pinfunction "GATE_15") (pintype "bidirectional"))
      (node (ref "U$21") (pin "16") (pinfunction "GATE_16") (pintype "bidirectional"))
      (node (ref "U$23") (pin "15") (pinfunction "GATE_15") (pintype "bidirectional"))
      (node (ref "U$23") (pin "16") (pinfunction "GATE_16") (pintype "bidirectional"))
      (node (ref "U$24") (pin "15") (pinfunction "GATE_15") (pintype "bidirectional"))
      (node (ref "U$24") (pin "16") (pinfunction "GATE_16") (pintype "bidirectional"))
      (node (ref "U$25") (pin "15") (pinfunction "GATE_15") (pintype "bidirectional"))
      (node (ref "U$25") (pin "16") (pinfunction "GATE_16") (pintype "bidirectional"))
      (node (ref "U$26") (pin "15") (pinfunction "GATE_15") (pintype "bidirectional"))
      (node (ref "U$26") (pin "16") (pinfunction "GATE_16") (pintype "bidirectional"))
      (node (ref "U$27") (pin "15") (pinfunction "GATE_15") (pintype "bidirectional"))
      (node (ref "U$27") (pin "16") (pinfunction "GATE_16") (pintype "bidirectional"))
      (node (ref "U$28") (pin "15") (pinfunction "GATE_15") (pintype "bidirectional"))
      (node (ref "U$28") (pin "16") (pinfunction "GATE_16") (pintype "bidirectional"))
      (node (ref "U$29") (pin "15") (pinfunction "GATE_15") (pintype "bidirectional"))
      (node (ref "U$29") (pin "16") (pinfunction "GATE_16") (pintype "bidirectional"))
      (node (ref "U$3") (pin "15") (pinfunction "GATE_15") (pintype "bidirectional"))
      (node (ref "U$3") (pin "16") (pinfunction "GATE_16") (pintype "bidirectional"))
      (node (ref "U$30") (pin "15") (pinfunction "GATE_15") (pintype "bidirectional"))
      (node (ref "U$30") (pin "16") (pinfunction "GATE_16") (pintype "bidirectional"))
      (node (ref "U$31") (pin "15") (pinfunction "GATE_15") (pintype "bidirectional"))
      (node (ref "U$31") (pin "16") (pinfunction "GATE_16") (pintype "bidirectional"))
      (node (ref "U$32") (pin "15") (pinfunction "GATE_15") (pintype "bidirectional"))
      (node (ref "U$32") (pin "16") (pinfunction "GATE_16") (pintype "bidirectional"))
      (node (ref "U$4") (pin "15") (pinfunction "GATE_15") (pintype "bidirectional"))
      (node (ref "U$4") (pin "16") (pinfunction "GATE_16") (pintype "bidirectional"))
      (node (ref "U$5") (pin "15") (pinfunction "GATE_15") (pintype "bidirectional"))
      (node (ref "U$5") (pin "16") (pinfunction "GATE_16") (pintype "bidirectional"))
      (node (ref "U$6") (pin "15") (pinfunction "GATE_15") (pintype "bidirectional"))
      (node (ref "U$6") (pin "16") (pinfunction "GATE_16") (pintype "bidirectional"))
      (node (ref "U$7") (pin "15") (pinfunction "GATE_15") (pintype "bidirectional"))
      (node (ref "U$7") (pin "16") (pinfunction "GATE_16") (pintype "bidirectional"))
      (node (ref "U$8") (pin "15") (pinfunction "GATE_15") (pintype "bidirectional"))
      (node (ref "U$8") (pin "16") (pinfunction "GATE_16") (pintype "bidirectional"))
      (node (ref "U$9") (pin "15") (pinfunction "GATE_15") (pintype "bidirectional"))
      (node (ref "U$9") (pin "16") (pinfunction "GATE_16") (pintype "bidirectional"))
    )
    (net (code "6") (name "GND") (class "Default")
      (node (ref "C1") (pin "-") (pinfunction "-_-") (pintype "passive"))
      (node (ref "C10") (pin "1") (pinfunction "1_1") (pintype "bidirectional"))
      (node (ref "C11") (pin "1") (pinfunction "1_1") (pintype "bidirectional"))
      (node (ref "C12") (pin "1") (pinfunction "1_1") (pintype "bidirectional"))
      (node (ref "C13") (pin "1") (pinfunction "1_1") (pintype "bidirectional"))
      (node (ref "C14") (pin "1") (pinfunction "1_1") (pintype "bidirectional"))
      (node (ref "C15") (pin "1") (pinfunction "1_1") (pintype "bidirectional"))
      (node (ref "C16") (pin "1") (pinfunction "1_1") (pintype "bidirectional"))
      (node (ref "C17") (pin "1") (pinfunction "1_1") (pintype "bidirectional"))
      (node (ref "C18") (pin "1") (pinfunction "1_1") (pintype "bidirectional"))
      (node (ref "C2") (pin "+") (pinfunction "+_+") (pintype "passive"))
      (node (ref "C3") (pin "-") (pinfunction "-_-") (pintype "passive"))
      (node (ref "C4") (pin "-") (pinfunction "-_-") (pintype "passive"))
      (node (ref "C5") (pin "+") (pinfunction "+_+") (pintype "passive"))
      (node (ref "C6") (pin "-") (pinfunction "-_-") (pintype "passive"))
      (node (ref "C7") (pin "1") (pinfunction "1_1") (pintype "bidirectional"))
      (node (ref "C8") (pin "1") (pinfunction "1_1") (pintype "bidirectional"))
      (node (ref "C9") (pin "1") (pinfunction "1_1") (pintype "bidirectional"))
      (node (ref "D2") (pin "-") (pinfunction "-_-") (pintype "passive"))
      (node (ref "D3") (pin "-") (pinfunction "-_-") (pintype "passive"))
      (node (ref "R1") (pin "1") (pinfunction "1_1") (pintype "bidirectional"))
      (node (ref "U$1") (pin "3") (pinfunction "GND_3") (pintype "bidirectional"))
      (node (ref "U$1") (pin "4") (pinfunction "GND_4") (pintype "bidirectional"))
      (node (ref "U$1") (pin "5") (pinfunction "GND_5") (pintype "bidirectional"))
      (node (ref "U$1") (pin "6") (pinfunction "GND_6") (pintype "bidirectional"))
      (node (ref "U$1") (pin "7") (pinfunction "GND_7") (pintype "bidirectional"))
      (node (ref "U$1") (pin "8") (pinfunction "GND_8") (pintype "bidirectional"))
      (node (ref "U$10") (pin "3") (pinfunction "GND_3") (pintype "bidirectional"))
      (node (ref "U$10") (pin "4") (pinfunction "GND_4") (pintype "bidirectional"))
      (node (ref "U$10") (pin "5") (pinfunction "GND_5") (pintype "bidirectional"))
      (node (ref "U$10") (pin "6") (pinfunction "GND_6") (pintype "bidirectional"))
      (node (ref "U$10") (pin "7") (pinfunction "GND_7") (pintype "bidirectional"))
      (node (ref "U$10") (pin "8") (pinfunction "GND_8") (pintype "bidirectional"))
      (node (ref "U$11") (pin "3") (pinfunction "GND_3") (pintype "bidirectional"))
      (node (ref "U$11") (pin "4") (pinfunction "GND_4") (pintype "bidirectional"))
      (node (ref "U$11") (pin "5") (pinfunction "GND_5") (pintype "bidirectional"))
      (node (ref "U$11") (pin "6") (pinfunction "GND_6") (pintype "bidirectional"))
      (node (ref "U$11") (pin "7") (pinfunction "GND_7") (pintype "bidirectional"))
      (node (ref "U$11") (pin "8") (pinfunction "GND_8") (pintype "bidirectional"))
      (node (ref "U$12") (pin "3") (pinfunction "GND_3") (pintype "bidirectional"))
      (node (ref "U$12") (pin "4") (pinfunction "GND_4") (pintype "bidirectional"))
      (node (ref "U$12") (pin "5") (pinfunction "GND_5") (pintype "bidirectional"))
      (node (ref "U$12") (pin "6") (pinfunction "GND_6") (pintype "bidirectional"))
      (node (ref "U$12") (pin "7") (pinfunction "GND_7") (pintype "bidirectional"))
      (node (ref "U$12") (pin "8") (pinfunction "GND_8") (pintype "bidirectional"))
      (node (ref "U$13") (pin "3") (pinfunction "GND_3") (pintype "bidirectional"))
      (node (ref "U$13") (pin "4") (pinfunction "GND_4") (pintype "bidirectional"))
      (node (ref "U$13") (pin "5") (pinfunction "GND_5") (pintype "bidirectional"))
      (node (ref "U$13") (pin "6") (pinfunction "GND_6") (pintype "bidirectional"))
      (node (ref "U$13") (pin "7") (pinfunction "GND_7") (pintype "bidirectional"))
      (node (ref "U$13") (pin "8") (pinfunction "GND_8") (pintype "bidirectional"))
      (node (ref "U$14") (pin "3") (pinfunction "GND_3") (pintype "bidirectional"))
      (node (ref "U$14") (pin "4") (pinfunction "GND_4") (pintype "bidirectional"))
      (node (ref "U$14") (pin "5") (pinfunction "GND_5") (pintype "bidirectional"))
      (node (ref "U$14") (pin "6") (pinfunction "GND_6") (pintype "bidirectional"))
      (node (ref "U$14") (pin "7") (pinfunction "GND_7") (pintype "bidirectional"))
      (node (ref "U$14") (pin "8") (pinfunction "GND_8") (pintype "bidirectional"))
      (node (ref "U$15") (pin "3") (pinfunction "GND_3") (pintype "bidirectional"))
      (node (ref "U$15") (pin "4") (pinfunction "GND_4") (pintype "bidirectional"))
      (node (ref "U$15") (pin "5") (pinfunction "GND_5") (pintype "bidirectional"))
      (node (ref "U$15") (pin "6") (pinfunction "GND_6") (pintype "bidirectional"))
      (node (ref "U$15") (pin "7") (pinfunction "GND_7") (pintype "bidirectional"))
      (node (ref "U$15") (pin "8") (pinfunction "GND_8") (pintype "bidirectional"))
      (node (ref "U$16") (pin "3") (pinfunction "GND_3") (pintype "bidirectional"))
      (node (ref "U$16") (pin "4") (pinfunction "GND_4") (pintype "bidirectional"))
      (node (ref "U$16") (pin "5") (pinfunction "GND_5") (pintype "bidirectional"))
      (node (ref "U$16") (pin "6") (pinfunction "GND_6") (pintype "bidirectional"))
      (node (ref "U$16") (pin "7") (pinfunction "GND_7") (pintype "bidirectional"))
      (node (ref "U$16") (pin "8") (pinfunction "GND_8") (pintype "bidirectional"))
      (node (ref "U$17") (pin "3") (pinfunction "GND_3") (pintype "bidirectional"))
      (node (ref "U$17") (pin "4") (pinfunction "GND_4") (pintype "bidirectional"))
      (node (ref "U$17") (pin "5") (pinfunction "GND_5") (pintype "bidirectional"))
      (node (ref "U$17") (pin "6") (pinfunction "GND_6") (pintype "bidirectional"))
      (node (ref "U$17") (pin "7") (pinfunction "GND_7") (pintype "bidirectional"))
      (node (ref "U$17") (pin "8") (pinfunction "GND_8") (pintype "bidirectional"))
      (node (ref "U$18") (pin "3") (pinfunction "GND_3") (pintype "bidirectional"))
      (node (ref "U$18") (pin "4") (pinfunction "GND_4") (pintype "bidirectional"))
      (node (ref "U$18") (pin "5") (pinfunction "GND_5") (pintype "bidirectional"))
      (node (ref "U$18") (pin "6") (pinfunction "GND_6") (pintype "bidirectional"))
      (node (ref "U$18") (pin "7") (pinfunction "GND_7") (pintype "bidirectional"))
      (node (ref "U$18") (pin "8") (pinfunction "GND_8") (pintype "bidirectional"))
      (node (ref "U$19") (pin "2") (pinfunction "2_2") (pintype "bidirectional"))
      (node (ref "U$2") (pin "3") (pinfunction "GND_3") (pintype "bidirectional"))
      (node (ref "U$2") (pin "4") (pinfunction "GND_4") (pintype "bidirectional"))
      (node (ref "U$2") (pin "5") (pinfunction "GND_5") (pintype "bidirectional"))
      (node (ref "U$2") (pin "6") (pinfunction "GND_6") (pintype "bidirectional"))
      (node (ref "U$2") (pin "7") (pinfunction "GND_7") (pintype "bidirectional"))
      (node (ref "U$2") (pin "8") (pinfunction "GND_8") (pintype "bidirectional"))
      (node (ref "U$20") (pin "3") (pinfunction "GND_3") (pintype "bidirectional"))
      (node (ref "U$20") (pin "4") (pinfunction "GND_4") (pintype "bidirectional"))
      (node (ref "U$20") (pin "5") (pinfunction "GND_5") (pintype "bidirectional"))
      (node (ref "U$20") (pin "6") (pinfunction "GND_6") (pintype "bidirectional"))
      (node (ref "U$20") (pin "7") (pinfunction "GND_7") (pintype "bidirectional"))
      (node (ref "U$20") (pin "8") (pinfunction "GND_8") (pintype "bidirectional"))
      (node (ref "U$21") (pin "3") (pinfunction "GND_3") (pintype "bidirectional"))
      (node (ref "U$21") (pin "4") (pinfunction "GND_4") (pintype "bidirectional"))
      (node (ref "U$21") (pin "5") (pinfunction "GND_5") (pintype "bidirectional"))
      (node (ref "U$21") (pin "6") (pinfunction "GND_6") (pintype "bidirectional"))
      (node (ref "U$21") (pin "7") (pinfunction "GND_7") (pintype "bidirectional"))
      (node (ref "U$21") (pin "8") (pinfunction "GND_8") (pintype "bidirectional"))
      (node (ref "U$22") (pin "3") (pinfunction "3_3") (pintype "bidirectional"))
      (node (ref "U$23") (pin "3") (pinfunction "GND_3") (pintype "bidirectional"))
      (node (ref "U$23") (pin "4") (pinfunction "GND_4") (pintype "bidirectional"))
      (node (ref "U$23") (pin "5") (pinfunction "GND_5") (pintype "bidirectional"))
      (node (ref "U$23") (pin "6") (pinfunction "GND_6") (pintype "bidirectional"))
      (node (ref "U$23") (pin "7") (pinfunction "GND_7") (pintype "bidirectional"))
      (node (ref "U$23") (pin "8") (pinfunction "GND_8") (pintype "bidirectional"))
      (node (ref "U$24") (pin "3") (pinfunction "GND_3") (pintype "bidirectional"))
      (node (ref "U$24") (pin "4") (pinfunction "GND_4") (pintype "bidirectional"))
      (node (ref "U$24") (pin "5") (pinfunction "GND_5") (pintype "bidirectional"))
      (node (ref "U$24") (pin "6") (pinfunction "GND_6") (pintype "bidirectional"))
      (node (ref "U$24") (pin "7") (pinfunction "GND_7") (pintype "bidirectional"))
      (node (ref "U$24") (pin "8") (pinfunction "GND_8") (pintype "bidirectional"))
      (node (ref "U$25") (pin "3") (pinfunction "GND_3") (pintype "bidirectional"))
      (node (ref "U$25") (pin "4") (pinfunction "GND_4") (pintype "bidirectional"))
      (node (ref "U$25") (pin "5") (pinfunction "GND_5") (pintype "bidirectional"))
      (node (ref "U$25") (pin "6") (pinfunction "GND_6") (pintype "bidirectional"))
      (node (ref "U$25") (pin "7") (pinfunction "GND_7") (pintype "bidirectional"))
      (node (ref "U$25") (pin "8") (pinfunction "GND_8") (pintype "bidirectional"))
      (node (ref "U$26") (pin "3") (pinfunction "GND_3") (pintype "bidirectional"))
      (node (ref "U$26") (pin "4") (pinfunction "GND_4") (pintype "bidirectional"))
      (node (ref "U$26") (pin "5") (pinfunction "GND_5") (pintype "bidirectional"))
      (node (ref "U$26") (pin "6") (pinfunction "GND_6") (pintype "bidirectional"))
      (node (ref "U$26") (pin "7") (pinfunction "GND_7") (pintype "bidirectional"))
      (node (ref "U$26") (pin "8") (pinfunction "GND_8") (pintype "bidirectional"))
      (node (ref "U$27") (pin "3") (pinfunction "GND_3") (pintype "bidirectional"))
      (node (ref "U$27") (pin "4") (pinfunction "GND_4") (pintype "bidirectional"))
      (node (ref "U$27") (pin "5") (pinfunction "GND_5") (pintype "bidirectional"))
      (node (ref "U$27") (pin "6") (pinfunction "GND_6") (pintype "bidirectional"))
      (node (ref "U$27") (pin "7") (pinfunction "GND_7") (pintype "bidirectional"))
      (node (ref "U$27") (pin "8") (pinfunction "GND_8") (pintype "bidirectional"))
      (node (ref "U$28") (pin "3") (pinfunction "GND_3") (pintype "bidirectional"))
      (node (ref "U$28") (pin "4") (pinfunction "GND_4") (pintype "bidirectional"))
      (node (ref "U$28") (pin "5") (pinfunction "GND_5") (pintype "bidirectional"))
      (node (ref "U$28") (pin "6") (pinfunction "GND_6") (pintype "bidirectional"))
      (node (ref "U$28") (pin "7") (pinfunction "GND_7") (pintype "bidirectional"))
      (node (ref "U$28") (pin "8") (pinfunction "GND_8") (pintype "bidirectional"))
      (node (ref "U$29") (pin "3") (pinfunction "GND_3") (pintype "bidirectional"))
      (node (ref "U$29") (pin "4") (pinfunction "GND_4") (pintype "bidirectional"))
      (node (ref "U$29") (pin "5") (pinfunction "GND_5") (pintype "bidirectional"))
      (node (ref "U$29") (pin "6") (pinfunction "GND_6") (pintype "bidirectional"))
      (node (ref "U$29") (pin "7") (pinfunction "GND_7") (pintype "bidirectional"))
      (node (ref "U$29") (pin "8") (pinfunction "GND_8") (pintype "bidirectional"))
      (node (ref "U$3") (pin "3") (pinfunction "GND_3") (pintype "bidirectional"))
      (node (ref "U$3") (pin "4") (pinfunction "GND_4") (pintype "bidirectional"))
      (node (ref "U$3") (pin "5") (pinfunction "GND_5") (pintype "bidirectional"))
      (node (ref "U$3") (pin "6") (pinfunction "GND_6") (pintype "bidirectional"))
      (node (ref "U$3") (pin "7") (pinfunction "GND_7") (pintype "bidirectional"))
      (node (ref "U$3") (pin "8") (pinfunction "GND_8") (pintype "bidirectional"))
      (node (ref "U$30") (pin "3") (pinfunction "GND_3") (pintype "bidirectional"))
      (node (ref "U$30") (pin "4") (pinfunction "GND_4") (pintype "bidirectional"))
      (node (ref "U$30") (pin "5") (pinfunction "GND_5") (pintype "bidirectional"))
      (node (ref "U$30") (pin "6") (pinfunction "GND_6") (pintype "bidirectional"))
      (node (ref "U$30") (pin "7") (pinfunction "GND_7") (pintype "bidirectional"))
      (node (ref "U$30") (pin "8") (pinfunction "GND_8") (pintype "bidirectional"))
      (node (ref "U$31") (pin "3") (pinfunction "GND_3") (pintype "bidirectional"))
      (node (ref "U$31") (pin "4") (pinfunction "GND_4") (pintype "bidirectional"))
      (node (ref "U$31") (pin "5") (pinfunction "GND_5") (pintype "bidirectional"))
      (node (ref "U$31") (pin "6") (pinfunction "GND_6") (pintype "bidirectional"))
      (node (ref "U$31") (pin "7") (pinfunction "GND_7") (pintype "bidirectional"))
      (node (ref "U$31") (pin "8") (pinfunction "GND_8") (pintype "bidirectional"))
      (node (ref "U$32") (pin "3") (pinfunction "GND_3") (pintype "bidirectional"))
      (node (ref "U$32") (pin "4") (pinfunction "GND_4") (pintype "bidirectional"))
      (node (ref "U$32") (pin "5") (pinfunction "GND_5") (pintype "bidirectional"))
      (node (ref "U$32") (pin "6") (pinfunction "GND_6") (pintype "bidirectional"))
      (node (ref "U$32") (pin "7") (pinfunction "GND_7") (pintype "bidirectional"))
      (node (ref "U$32") (pin "8") (pinfunction "GND_8") (pintype "bidirectional"))
      (node (ref "U$4") (pin "3") (pinfunction "GND_3") (pintype "bidirectional"))
      (node (ref "U$4") (pin "4") (pinfunction "GND_4") (pintype "bidirectional"))
      (node (ref "U$4") (pin "5") (pinfunction "GND_5") (pintype "bidirectional"))
      (node (ref "U$4") (pin "6") (pinfunction "GND_6") (pintype "bidirectional"))
      (node (ref "U$4") (pin "7") (pinfunction "GND_7") (pintype "bidirectional"))
      (node (ref "U$4") (pin "8") (pinfunction "GND_8") (pintype "bidirectional"))
      (node (ref "U$5") (pin "3") (pinfunction "GND_3") (pintype "bidirectional"))
      (node (ref "U$5") (pin "4") (pinfunction "GND_4") (pintype "bidirectional"))
      (node (ref "U$5") (pin "5") (pinfunction "GND_5") (pintype "bidirectional"))
      (node (ref "U$5") (pin "6") (pinfunction "GND_6") (pintype "bidirectional"))
      (node (ref "U$5") (pin "7") (pinfunction "GND_7") (pintype "bidirectional"))
      (node (ref "U$5") (pin "8") (pinfunction "GND_8") (pintype "bidirectional"))
      (node (ref "U$6") (pin "3") (pinfunction "GND_3") (pintype "bidirectional"))
      (node (ref "U$6") (pin "4") (pinfunction "GND_4") (pintype "bidirectional"))
      (node (ref "U$6") (pin "5") (pinfunction "GND_5") (pintype "bidirectional"))
      (node (ref "U$6") (pin "6") (pinfunction "GND_6") (pintype "bidirectional"))
      (node (ref "U$6") (pin "7") (pinfunction "GND_7") (pintype "bidirectional"))
      (node (ref "U$6") (pin "8") (pinfunction "GND_8") (pintype "bidirectional"))
      (node (ref "U$7") (pin "3") (pinfunction "GND_3") (pintype "bidirectional"))
      (node (ref "U$7") (pin "4") (pinfunction "GND_4") (pintype "bidirectional"))
      (node (ref "U$7") (pin "5") (pinfunction "GND_5") (pintype "bidirectional"))
      (node (ref "U$7") (pin "6") (pinfunction "GND_6") (pintype "bidirectional"))
      (node (ref "U$7") (pin "7") (pinfunction "GND_7") (pintype "bidirectional"))
      (node (ref "U$7") (pin "8") (pinfunction "GND_8") (pintype "bidirectional"))
      (node (ref "U$8") (pin "3") (pinfunction "GND_3") (pintype "bidirectional"))
      (node (ref "U$8") (pin "4") (pinfunction "GND_4") (pintype "bidirectional"))
      (node (ref "U$8") (pin "5") (pinfunction "GND_5") (pintype "bidirectional"))
      (node (ref "U$8") (pin "6") (pinfunction "GND_6") (pintype "bidirectional"))
      (node (ref "U$8") (pin "7") (pinfunction "GND_7") (pintype "bidirectional"))
      (node (ref "U$8") (pin "8") (pinfunction "GND_8") (pintype "bidirectional"))
      (node (ref "U$9") (pin "3") (pinfunction "GND_3") (pintype "bidirectional"))
      (node (ref "U$9") (pin "4") (pinfunction "GND_4") (pintype "bidirectional"))
      (node (ref "U$9") (pin "5") (pinfunction "GND_5") (pintype "bidirectional"))
      (node (ref "U$9") (pin "6") (pinfunction "GND_6") (pintype "bidirectional"))
      (node (ref "U$9") (pin "7") (pinfunction "GND_7") (pintype "bidirectional"))
      (node (ref "U$9") (pin "8") (pinfunction "GND_8") (pintype "bidirectional"))
    )
    (net (code "7") (name "Net-(D1-Pad+)") (class "Default")
      (node (ref "D1") (pin "+") (pinfunction "+_+") (pintype "passive"))
      (node (ref "R1") (pin "2") (pinfunction "2_2") (pintype "bidirectional"))
    )
    (net (code "8") (name "Net-(D2-Pad+)") (class "Default")
      (node (ref "D2") (pin "+") (pinfunction "+_+") (pintype "passive"))
      (node (ref "R2") (pin "2") (pinfunction "2_2") (pintype "bidirectional"))
    )
    (net (code "9") (name "Net-(D3-Pad+)") (class "Default")
      (node (ref "D3") (pin "+") (pinfunction "+_+") (pintype "passive"))
      (node (ref "R3") (pin "2") (pinfunction "2_2") (pintype "bidirectional"))
    )
  )
)
